# EuroCard_Backplane.net
KiCad netlist of a schematic drawn in EAGLE
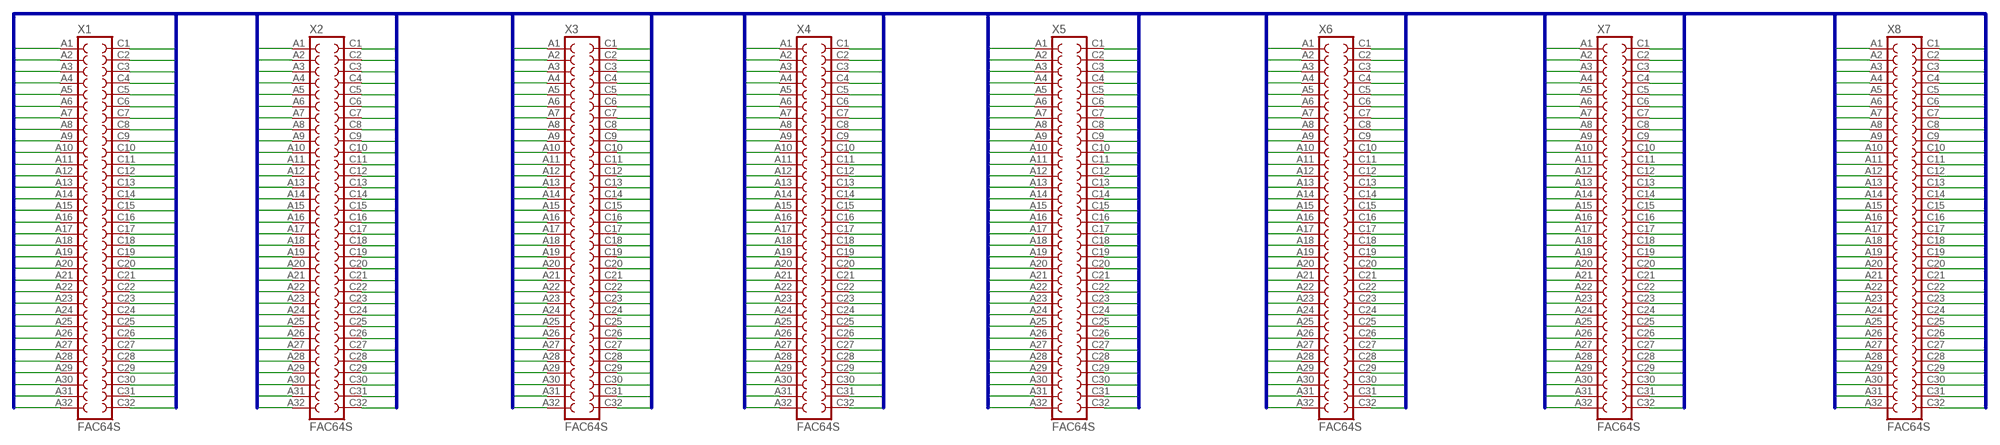
[diagram p0: schematic, sheet 1]

(export (version "E")
  (design (tool "Eeschema 10.0.6"))
  (components
    (comp (ref "X1")
      (value "FAC64S")
      (footprint "eagle-import:FAC64S")
      (libsource (lib "eagle-import") (part "FAC64S"))
    )
    (comp (ref "X2")
      (value "FAC64S")
      (footprint "eagle-import:FAC64S")
      (libsource (lib "eagle-import") (part "FAC64S"))
    )
    (comp (ref "X3")
      (value "FAC64S")
      (footprint "eagle-import:FAC64S")
      (libsource (lib "eagle-import") (part "FAC64S"))
    )
    (comp (ref "X4")
      (value "FAC64S")
      (footprint "eagle-import:FAC64S")
      (libsource (lib "eagle-import") (part "FAC64S"))
    )
    (comp (ref "X5")
      (value "FAC64S")
      (footprint "eagle-import:FAC64S")
      (libsource (lib "eagle-import") (part "FAC64S"))
    )
    (comp (ref "X6")
      (value "FAC64S")
      (footprint "eagle-import:FAC64S")
      (libsource (lib "eagle-import") (part "FAC64S"))
    )
    (comp (ref "X7")
      (value "FAC64S")
      (footprint "eagle-import:FAC64S")
      (libsource (lib "eagle-import") (part "FAC64S"))
    )
    (comp (ref "X8")
      (value "FAC64S")
      (footprint "eagle-import:FAC64S")
      (libsource (lib "eagle-import") (part "FAC64S"))
    )
  )
  (nets
    (net (code "1") (name "/A1") (class "Default")
      (node (ref "X1") (pin "A1") (pinfunction "A1_A1") (pintype "passive"))
      (node (ref "X2") (pin "A1") (pinfunction "A1_A1") (pintype "passive"))
      (node (ref "X3") (pin "A1") (pinfunction "A1_A1") (pintype "passive"))
      (node (ref "X4") (pin "A1") (pinfunction "A1_A1") (pintype "passive"))
      (node (ref "X5") (pin "A1") (pinfunction "A1_A1") (pintype "passive"))
      (node (ref "X6") (pin "A1") (pinfunction "A1_A1") (pintype "passive"))
      (node (ref "X7") (pin "A1") (pinfunction "A1_A1") (pintype "passive"))
      (node (ref "X8") (pin "A1") (pinfunction "A1_A1") (pintype "passive"))
    )
    (net (code "2") (name "/A2") (class "Default")
      (node (ref "X1") (pin "A2") (pinfunction "A2_A2") (pintype "passive"))
      (node (ref "X2") (pin "A2") (pinfunction "A2_A2") (pintype "passive"))
      (node (ref "X3") (pin "A2") (pinfunction "A2_A2") (pintype "passive"))
      (node (ref "X4") (pin "A2") (pinfunction "A2_A2") (pintype "passive"))
      (node (ref "X5") (pin "A2") (pinfunction "A2_A2") (pintype "passive"))
      (node (ref "X6") (pin "A2") (pinfunction "A2_A2") (pintype "passive"))
      (node (ref "X7") (pin "A2") (pinfunction "A2_A2") (pintype "passive"))
      (node (ref "X8") (pin "A2") (pinfunction "A2_A2") (pintype "passive"))
    )
    (net (code "3") (name "/A3") (class "Default")
      (node (ref "X1") (pin "A3") (pinfunction "A3_A3") (pintype "passive"))
      (node (ref "X2") (pin "A3") (pinfunction "A3_A3") (pintype "passive"))
      (node (ref "X3") (pin "A3") (pinfunction "A3_A3") (pintype "passive"))
      (node (ref "X4") (pin "A3") (pinfunction "A3_A3") (pintype "passive"))
      (node (ref "X5") (pin "A3") (pinfunction "A3_A3") (pintype "passive"))
      (node (ref "X6") (pin "A3") (pinfunction "A3_A3") (pintype "passive"))
      (node (ref "X7") (pin "A3") (pinfunction "A3_A3") (pintype "passive"))
      (node (ref "X8") (pin "A3") (pinfunction "A3_A3") (pintype "passive"))
    )
    (net (code "4") (name "/A4") (class "Default")
      (node (ref "X1") (pin "A4") (pinfunction "A4_A4") (pintype "passive"))
      (node (ref "X2") (pin "A4") (pinfunction "A4_A4") (pintype "passive"))
      (node (ref "X3") (pin "A4") (pinfunction "A4_A4") (pintype "passive"))
      (node (ref "X4") (pin "A4") (pinfunction "A4_A4") (pintype "passive"))
      (node (ref "X5") (pin "A4") (pinfunction "A4_A4") (pintype "passive"))
      (node (ref "X6") (pin "A4") (pinfunction "A4_A4") (pintype "passive"))
      (node (ref "X7") (pin "A4") (pinfunction "A4_A4") (pintype "passive"))
      (node (ref "X8") (pin "A4") (pinfunction "A4_A4") (pintype "passive"))
    )
    (net (code "5") (name "/A5") (class "Default")
      (node (ref "X1") (pin "A5") (pinfunction "A5_A5") (pintype "passive"))
      (node (ref "X2") (pin "A5") (pinfunction "A5_A5") (pintype "passive"))
      (node (ref "X3") (pin "A5") (pinfunction "A5_A5") (pintype "passive"))
      (node (ref "X4") (pin "A5") (pinfunction "A5_A5") (pintype "passive"))
      (node (ref "X5") (pin "A5") (pinfunction "A5_A5") (pintype "passive"))
      (node (ref "X6") (pin "A5") (pinfunction "A5_A5") (pintype "passive"))
      (node (ref "X7") (pin "A5") (pinfunction "A5_A5") (pintype "passive"))
      (node (ref "X8") (pin "A5") (pinfunction "A5_A5") (pintype "passive"))
    )
    (net (code "6") (name "/A6") (class "Default")
      (node (ref "X1") (pin "A6") (pinfunction "A6_A6") (pintype "passive"))
      (node (ref "X2") (pin "A6") (pinfunction "A6_A6") (pintype "passive"))
      (node (ref "X3") (pin "A6") (pinfunction "A6_A6") (pintype "passive"))
      (node (ref "X4") (pin "A6") (pinfunction "A6_A6") (pintype "passive"))
      (node (ref "X5") (pin "A6") (pinfunction "A6_A6") (pintype "passive"))
      (node (ref "X6") (pin "A6") (pinfunction "A6_A6") (pintype "passive"))
      (node (ref "X7") (pin "A6") (pinfunction "A6_A6") (pintype "passive"))
      (node (ref "X8") (pin "A6") (pinfunction "A6_A6") (pintype "passive"))
    )
    (net (code "7") (name "/A7") (class "Default")
      (node (ref "X1") (pin "A7") (pinfunction "A7_A7") (pintype "passive"))
      (node (ref "X2") (pin "A7") (pinfunction "A7_A7") (pintype "passive"))
      (node (ref "X3") (pin "A7") (pinfunction "A7_A7") (pintype "passive"))
      (node (ref "X4") (pin "A7") (pinfunction "A7_A7") (pintype "passive"))
      (node (ref "X5") (pin "A7") (pinfunction "A7_A7") (pintype "passive"))
      (node (ref "X6") (pin "A7") (pinfunction "A7_A7") (pintype "passive"))
      (node (ref "X7") (pin "A7") (pinfunction "A7_A7") (pintype "passive"))
      (node (ref "X8") (pin "A7") (pinfunction "A7_A7") (pintype "passive"))
    )
    (net (code "8") (name "/A8") (class "Default")
      (node (ref "X1") (pin "A8") (pinfunction "A8_A8") (pintype "passive"))
      (node (ref "X2") (pin "A8") (pinfunction "A8_A8") (pintype "passive"))
      (node (ref "X3") (pin "A8") (pinfunction "A8_A8") (pintype "passive"))
      (node (ref "X4") (pin "A8") (pinfunction "A8_A8") (pintype "passive"))
      (node (ref "X5") (pin "A8") (pinfunction "A8_A8") (pintype "passive"))
      (node (ref "X6") (pin "A8") (pinfunction "A8_A8") (pintype "passive"))
      (node (ref "X7") (pin "A8") (pinfunction "A8_A8") (pintype "passive"))
      (node (ref "X8") (pin "A8") (pinfunction "A8_A8") (pintype "passive"))
    )
    (net (code "9") (name "/A9") (class "Default")
      (node (ref "X1") (pin "A9") (pinfunction "A9_A9") (pintype "passive"))
      (node (ref "X2") (pin "A9") (pinfunction "A9_A9") (pintype "passive"))
      (node (ref "X3") (pin "A9") (pinfunction "A9_A9") (pintype "passive"))
      (node (ref "X4") (pin "A9") (pinfunction "A9_A9") (pintype "passive"))
      (node (ref "X5") (pin "A9") (pinfunction "A9_A9") (pintype "passive"))
      (node (ref "X6") (pin "A9") (pinfunction "A9_A9") (pintype "passive"))
      (node (ref "X7") (pin "A9") (pinfunction "A9_A9") (pintype "passive"))
      (node (ref "X8") (pin "A9") (pinfunction "A9_A9") (pintype "passive"))
    )
    (net (code "10") (name "/A10") (class "Default")
      (node (ref "X1") (pin "A10") (pinfunction "A10_A10") (pintype "passive"))
      (node (ref "X2") (pin "A10") (pinfunction "A10_A10") (pintype "passive"))
      (node (ref "X3") (pin "A10") (pinfunction "A10_A10") (pintype "passive"))
      (node (ref "X4") (pin "A10") (pinfunction "A10_A10") (pintype "passive"))
      (node (ref "X5") (pin "A10") (pinfunction "A10_A10") (pintype "passive"))
      (node (ref "X6") (pin "A10") (pinfunction "A10_A10") (pintype "passive"))
      (node (ref "X7") (pin "A10") (pinfunction "A10_A10") (pintype "passive"))
      (node (ref "X8") (pin "A10") (pinfunction "A10_A10") (pintype "passive"))
    )
    (net (code "11") (name "/A11") (class "Default")
      (node (ref "X1") (pin "A11") (pinfunction "A11_A11") (pintype "passive"))
      (node (ref "X2") (pin "A11") (pinfunction "A11_A11") (pintype "passive"))
      (node (ref "X3") (pin "A11") (pinfunction "A11_A11") (pintype "passive"))
      (node (ref "X4") (pin "A11") (pinfunction "A11_A11") (pintype "passive"))
      (node (ref "X5") (pin "A11") (pinfunction "A11_A11") (pintype "passive"))
      (node (ref "X6") (pin "A11") (pinfunction "A11_A11") (pintype "passive"))
      (node (ref "X7") (pin "A11") (pinfunction "A11_A11") (pintype "passive"))
      (node (ref "X8") (pin "A11") (pinfunction "A11_A11") (pintype "passive"))
    )
    (net (code "12") (name "/A12") (class "Default")
      (node (ref "X1") (pin "A12") (pinfunction "A12_A12") (pintype "passive"))
      (node (ref "X2") (pin "A12") (pinfunction "A12_A12") (pintype "passive"))
      (node (ref "X3") (pin "A12") (pinfunction "A12_A12") (pintype "passive"))
      (node (ref "X4") (pin "A12") (pinfunction "A12_A12") (pintype "passive"))
      (node (ref "X5") (pin "A12") (pinfunction "A12_A12") (pintype "passive"))
      (node (ref "X6") (pin "A12") (pinfunction "A12_A12") (pintype "passive"))
      (node (ref "X7") (pin "A12") (pinfunction "A12_A12") (pintype "passive"))
      (node (ref "X8") (pin "A12") (pinfunction "A12_A12") (pintype "passive"))
    )
    (net (code "13") (name "/A13") (class "Default")
      (node (ref "X1") (pin "A13") (pinfunction "A13_A13") (pintype "passive"))
      (node (ref "X2") (pin "A13") (pinfunction "A13_A13") (pintype "passive"))
      (node (ref "X3") (pin "A13") (pinfunction "A13_A13") (pintype "passive"))
      (node (ref "X4") (pin "A13") (pinfunction "A13_A13") (pintype "passive"))
      (node (ref "X5") (pin "A13") (pinfunction "A13_A13") (pintype "passive"))
      (node (ref "X6") (pin "A13") (pinfunction "A13_A13") (pintype "passive"))
      (node (ref "X7") (pin "A13") (pinfunction "A13_A13") (pintype "passive"))
      (node (ref "X8") (pin "A13") (pinfunction "A13_A13") (pintype "passive"))
    )
    (net (code "14") (name "/A14") (class "Default")
      (node (ref "X1") (pin "A14") (pinfunction "A14_A14") (pintype "passive"))
      (node (ref "X2") (pin "A14") (pinfunction "A14_A14") (pintype "passive"))
      (node (ref "X3") (pin "A14") (pinfunction "A14_A14") (pintype "passive"))
      (node (ref "X4") (pin "A14") (pinfunction "A14_A14") (pintype "passive"))
      (node (ref "X5") (pin "A14") (pinfunction "A14_A14") (pintype "passive"))
      (node (ref "X6") (pin "A14") (pinfunction "A14_A14") (pintype "passive"))
      (node (ref "X7") (pin "A14") (pinfunction "A14_A14") (pintype "passive"))
      (node (ref "X8") (pin "A14") (pinfunction "A14_A14") (pintype "passive"))
    )
    (net (code "15") (name "/A15") (class "Default")
      (node (ref "X1") (pin "A15") (pinfunction "A15_A15") (pintype "passive"))
      (node (ref "X2") (pin "A15") (pinfunction "A15_A15") (pintype "passive"))
      (node (ref "X3") (pin "A15") (pinfunction "A15_A15") (pintype "passive"))
      (node (ref "X4") (pin "A15") (pinfunction "A15_A15") (pintype "passive"))
      (node (ref "X5") (pin "A15") (pinfunction "A15_A15") (pintype "passive"))
      (node (ref "X6") (pin "A15") (pinfunction "A15_A15") (pintype "passive"))
      (node (ref "X7") (pin "A15") (pinfunction "A15_A15") (pintype "passive"))
      (node (ref "X8") (pin "A15") (pinfunction "A15_A15") (pintype "passive"))
    )
    (net (code "16") (name "/A16") (class "Default")
      (node (ref "X1") (pin "A16") (pinfunction "A16_A16") (pintype "passive"))
      (node (ref "X2") (pin "A16") (pinfunction "A16_A16") (pintype "passive"))
      (node (ref "X3") (pin "A16") (pinfunction "A16_A16") (pintype "passive"))
      (node (ref "X4") (pin "A16") (pinfunction "A16_A16") (pintype "passive"))
      (node (ref "X5") (pin "A16") (pinfunction "A16_A16") (pintype "passive"))
      (node (ref "X6") (pin "A16") (pinfunction "A16_A16") (pintype "passive"))
      (node (ref "X7") (pin "A16") (pinfunction "A16_A16") (pintype "passive"))
      (node (ref "X8") (pin "A16") (pinfunction "A16_A16") (pintype "passive"))
    )
    (net (code "17") (name "/A17") (class "Default")
      (node (ref "X1") (pin "A17") (pinfunction "A17_A17") (pintype "passive"))
      (node (ref "X2") (pin "A17") (pinfunction "A17_A17") (pintype "passive"))
      (node (ref "X3") (pin "A17") (pinfunction "A17_A17") (pintype "passive"))
      (node (ref "X4") (pin "A17") (pinfunction "A17_A17") (pintype "passive"))
      (node (ref "X5") (pin "A17") (pinfunction "A17_A17") (pintype "passive"))
      (node (ref "X6") (pin "A17") (pinfunction "A17_A17") (pintype "passive"))
      (node (ref "X7") (pin "A17") (pinfunction "A17_A17") (pintype "passive"))
      (node (ref "X8") (pin "A17") (pinfunction "A17_A17") (pintype "passive"))
    )
    (net (code "18") (name "/A18") (class "Default")
      (node (ref "X1") (pin "A18") (pinfunction "A18_A18") (pintype "passive"))
      (node (ref "X2") (pin "A18") (pinfunction "A18_A18") (pintype "passive"))
      (node (ref "X3") (pin "A18") (pinfunction "A18_A18") (pintype "passive"))
      (node (ref "X4") (pin "A18") (pinfunction "A18_A18") (pintype "passive"))
      (node (ref "X5") (pin "A18") (pinfunction "A18_A18") (pintype "passive"))
      (node (ref "X6") (pin "A18") (pinfunction "A18_A18") (pintype "passive"))
      (node (ref "X7") (pin "A18") (pinfunction "A18_A18") (pintype "passive"))
      (node (ref "X8") (pin "A18") (pinfunction "A18_A18") (pintype "passive"))
    )
    (net (code "19") (name "/A19") (class "Default")
      (node (ref "X1") (pin "A19") (pinfunction "A19_A19") (pintype "passive"))
      (node (ref "X2") (pin "A19") (pinfunction "A19_A19") (pintype "passive"))
      (node (ref "X3") (pin "A19") (pinfunction "A19_A19") (pintype "passive"))
      (node (ref "X4") (pin "A19") (pinfunction "A19_A19") (pintype "passive"))
      (node (ref "X5") (pin "A19") (pinfunction "A19_A19") (pintype "passive"))
      (node (ref "X6") (pin "A19") (pinfunction "A19_A19") (pintype "passive"))
      (node (ref "X7") (pin "A19") (pinfunction "A19_A19") (pintype "passive"))
      (node (ref "X8") (pin "A19") (pinfunction "A19_A19") (pintype "passive"))
    )
    (net (code "20") (name "/A20") (class "Default")
      (node (ref "X1") (pin "A20") (pinfunction "A20_A20") (pintype "passive"))
      (node (ref "X2") (pin "A20") (pinfunction "A20_A20") (pintype "passive"))
      (node (ref "X3") (pin "A20") (pinfunction "A20_A20") (pintype "passive"))
      (node (ref "X4") (pin "A20") (pinfunction "A20_A20") (pintype "passive"))
      (node (ref "X5") (pin "A20") (pinfunction "A20_A20") (pintype "passive"))
      (node (ref "X6") (pin "A20") (pinfunction "A20_A20") (pintype "passive"))
      (node (ref "X7") (pin "A20") (pinfunction "A20_A20") (pintype "passive"))
      (node (ref "X8") (pin "A20") (pinfunction "A20_A20") (pintype "passive"))
    )
    (net (code "21") (name "/A21") (class "Default")
      (node (ref "X1") (pin "A21") (pinfunction "A21_A21") (pintype "passive"))
      (node (ref "X2") (pin "A21") (pinfunction "A21_A21") (pintype "passive"))
      (node (ref "X3") (pin "A21") (pinfunction "A21_A21") (pintype "passive"))
      (node (ref "X4") (pin "A21") (pinfunction "A21_A21") (pintype "passive"))
      (node (ref "X5") (pin "A21") (pinfunction "A21_A21") (pintype "passive"))
      (node (ref "X6") (pin "A21") (pinfunction "A21_A21") (pintype "passive"))
      (node (ref "X7") (pin "A21") (pinfunction "A21_A21") (pintype "passive"))
      (node (ref "X8") (pin "A21") (pinfunction "A21_A21") (pintype "passive"))
    )
    (net (code "22") (name "/A22") (class "Default")
      (node (ref "X1") (pin "A22") (pinfunction "A22_A22") (pintype "passive"))
      (node (ref "X2") (pin "A22") (pinfunction "A22_A22") (pintype "passive"))
      (node (ref "X3") (pin "A22") (pinfunction "A22_A22") (pintype "passive"))
      (node (ref "X4") (pin "A22") (pinfunction "A22_A22") (pintype "passive"))
      (node (ref "X5") (pin "A22") (pinfunction "A22_A22") (pintype "passive"))
      (node (ref "X6") (pin "A22") (pinfunction "A22_A22") (pintype "passive"))
      (node (ref "X7") (pin "A22") (pinfunction "A22_A22") (pintype "passive"))
      (node (ref "X8") (pin "A22") (pinfunction "A22_A22") (pintype "passive"))
    )
    (net (code "23") (name "/A23") (class "Default")
      (node (ref "X1") (pin "A23") (pinfunction "A23_A23") (pintype "passive"))
      (node (ref "X2") (pin "A23") (pinfunction "A23_A23") (pintype "passive"))
      (node (ref "X3") (pin "A23") (pinfunction "A23_A23") (pintype "passive"))
      (node (ref "X4") (pin "A23") (pinfunction "A23_A23") (pintype "passive"))
      (node (ref "X5") (pin "A23") (pinfunction "A23_A23") (pintype "passive"))
      (node (ref "X6") (pin "A23") (pinfunction "A23_A23") (pintype "passive"))
      (node (ref "X7") (pin "A23") (pinfunction "A23_A23") (pintype "passive"))
      (node (ref "X8") (pin "A23") (pinfunction "A23_A23") (pintype "passive"))
    )
    (net (code "24") (name "/A24") (class "Default")
      (node (ref "X1") (pin "A24") (pinfunction "A24_A24") (pintype "passive"))
      (node (ref "X2") (pin "A24") (pinfunction "A24_A24") (pintype "passive"))
      (node (ref "X3") (pin "A24") (pinfunction "A24_A24") (pintype "passive"))
      (node (ref "X4") (pin "A24") (pinfunction "A24_A24") (pintype "passive"))
      (node (ref "X5") (pin "A24") (pinfunction "A24_A24") (pintype "passive"))
      (node (ref "X6") (pin "A24") (pinfunction "A24_A24") (pintype "passive"))
      (node (ref "X7") (pin "A24") (pinfunction "A24_A24") (pintype "passive"))
      (node (ref "X8") (pin "A24") (pinfunction "A24_A24") (pintype "passive"))
    )
    (net (code "25") (name "/A25") (class "Default")
      (node (ref "X1") (pin "A25") (pinfunction "A25_A25") (pintype "passive"))
      (node (ref "X2") (pin "A25") (pinfunction "A25_A25") (pintype "passive"))
      (node (ref "X3") (pin "A25") (pinfunction "A25_A25") (pintype "passive"))
      (node (ref "X4") (pin "A25") (pinfunction "A25_A25") (pintype "passive"))
      (node (ref "X5") (pin "A25") (pinfunction "A25_A25") (pintype "passive"))
      (node (ref "X6") (pin "A25") (pinfunction "A25_A25") (pintype "passive"))
      (node (ref "X7") (pin "A25") (pinfunction "A25_A25") (pintype "passive"))
      (node (ref "X8") (pin "A25") (pinfunction "A25_A25") (pintype "passive"))
    )
    (net (code "26") (name "/A26") (class "Default")
      (node (ref "X1") (pin "A26") (pinfunction "A26_A26") (pintype "passive"))
      (node (ref "X2") (pin "A26") (pinfunction "A26_A26") (pintype "passive"))
      (node (ref "X3") (pin "A26") (pinfunction "A26_A26") (pintype "passive"))
      (node (ref "X4") (pin "A26") (pinfunction "A26_A26") (pintype "passive"))
      (node (ref "X5") (pin "A26") (pinfunction "A26_A26") (pintype "passive"))
      (node (ref "X6") (pin "A26") (pinfunction "A26_A26") (pintype "passive"))
      (node (ref "X7") (pin "A26") (pinfunction "A26_A26") (pintype "passive"))
      (node (ref "X8") (pin "A26") (pinfunction "A26_A26") (pintype "passive"))
    )
    (net (code "27") (name "/A27") (class "Default")
      (node (ref "X1") (pin "A27") (pinfunction "A27_A27") (pintype "passive"))
      (node (ref "X2") (pin "A27") (pinfunction "A27_A27") (pintype "passive"))
      (node (ref "X3") (pin "A27") (pinfunction "A27_A27") (pintype "passive"))
      (node (ref "X4") (pin "A27") (pinfunction "A27_A27") (pintype "passive"))
      (node (ref "X5") (pin "A27") (pinfunction "A27_A27") (pintype "passive"))
      (node (ref "X6") (pin "A27") (pinfunction "A27_A27") (pintype "passive"))
      (node (ref "X7") (pin "A27") (pinfunction "A27_A27") (pintype "passive"))
      (node (ref "X8") (pin "A27") (pinfunction "A27_A27") (pintype "passive"))
    )
    (net (code "28") (name "/A28") (class "Default")
      (node (ref "X1") (pin "A28") (pinfunction "A28_A28") (pintype "passive"))
      (node (ref "X2") (pin "A28") (pinfunction "A28_A28") (pintype "passive"))
      (node (ref "X3") (pin "A28") (pinfunction "A28_A28") (pintype "passive"))
      (node (ref "X4") (pin "A28") (pinfunction "A28_A28") (pintype "passive"))
      (node (ref "X5") (pin "A28") (pinfunction "A28_A28") (pintype "passive"))
      (node (ref "X6") (pin "A28") (pinfunction "A28_A28") (pintype "passive"))
      (node (ref "X7") (pin "A28") (pinfunction "A28_A28") (pintype "passive"))
      (node (ref "X8") (pin "A28") (pinfunction "A28_A28") (pintype "passive"))
    )
    (net (code "29") (name "/A29") (class "Default")
      (node (ref "X1") (pin "A29") (pinfunction "A29_A29") (pintype "passive"))
      (node (ref "X2") (pin "A29") (pinfunction "A29_A29") (pintype "passive"))
      (node (ref "X3") (pin "A29") (pinfunction "A29_A29") (pintype "passive"))
      (node (ref "X4") (pin "A29") (pinfunction "A29_A29") (pintype "passive"))
      (node (ref "X5") (pin "A29") (pinfunction "A29_A29") (pintype "passive"))
      (node (ref "X6") (pin "A29") (pinfunction "A29_A29") (pintype "passive"))
      (node (ref "X7") (pin "A29") (pinfunction "A29_A29") (pintype "passive"))
      (node (ref "X8") (pin "A29") (pinfunction "A29_A29") (pintype "passive"))
    )
    (net (code "30") (name "/A30") (class "Default")
      (node (ref "X1") (pin "A30") (pinfunction "A30_A30") (pintype "passive"))
      (node (ref "X2") (pin "A30") (pinfunction "A30_A30") (pintype "passive"))
      (node (ref "X3") (pin "A30") (pinfunction "A30_A30") (pintype "passive"))
      (node (ref "X4") (pin "A30") (pinfunction "A30_A30") (pintype "passive"))
      (node (ref "X5") (pin "A30") (pinfunction "A30_A30") (pintype "passive"))
      (node (ref "X6") (pin "A30") (pinfunction "A30_A30") (pintype "passive"))
      (node (ref "X7") (pin "A30") (pinfunction "A30_A30") (pintype "passive"))
      (node (ref "X8") (pin "A30") (pinfunction "A30_A30") (pintype "passive"))
    )
    (net (code "31") (name "/A31") (class "Default")
      (node (ref "X1") (pin "A31") (pinfunction "A31_A31") (pintype "passive"))
      (node (ref "X2") (pin "A31") (pinfunction "A31_A31") (pintype "passive"))
      (node (ref "X3") (pin "A31") (pinfunction "A31_A31") (pintype "passive"))
      (node (ref "X4") (pin "A31") (pinfunction "A31_A31") (pintype "passive"))
      (node (ref "X5") (pin "A31") (pinfunction "A31_A31") (pintype "passive"))
      (node (ref "X6") (pin "A31") (pinfunction "A31_A31") (pintype "passive"))
      (node (ref "X7") (pin "A31") (pinfunction "A31_A31") (pintype "passive"))
      (node (ref "X8") (pin "A31") (pinfunction "A31_A31") (pintype "passive"))
    )
    (net (code "32") (name "/A32") (class "Default")
      (node (ref "X1") (pin "A32") (pinfunction "A32_A32") (pintype "passive"))
      (node (ref "X2") (pin "A32") (pinfunction "A32_A32") (pintype "passive"))
      (node (ref "X3") (pin "A32") (pinfunction "A32_A32") (pintype "passive"))
      (node (ref "X4") (pin "A32") (pinfunction "A32_A32") (pintype "passive"))
      (node (ref "X5") (pin "A32") (pinfunction "A32_A32") (pintype "passive"))
      (node (ref "X6") (pin "A32") (pinfunction "A32_A32") (pintype "passive"))
      (node (ref "X7") (pin "A32") (pinfunction "A32_A32") (pintype "passive"))
      (node (ref "X8") (pin "A32") (pinfunction "A32_A32") (pintype "passive"))
    )
    (net (code "33") (name "/C1") (class "Default")
      (node (ref "X1") (pin "C1") (pinfunction "C1_C1") (pintype "passive"))
      (node (ref "X2") (pin "C1") (pinfunction "C1_C1") (pintype "passive"))
      (node (ref "X3") (pin "C1") (pinfunction "C1_C1") (pintype "passive"))
      (node (ref "X4") (pin "C1") (pinfunction "C1_C1") (pintype "passive"))
      (node (ref "X5") (pin "C1") (pinfunction "C1_C1") (pintype "passive"))
      (node (ref "X6") (pin "C1") (pinfunction "C1_C1") (pintype "passive"))
      (node (ref "X7") (pin "C1") (pinfunction "C1_C1") (pintype "passive"))
      (node (ref "X8") (pin "C1") (pinfunction "C1_C1") (pintype "passive"))
    )
    (net (code "34") (name "/C2") (class "Default")
      (node (ref "X1") (pin "C2") (pinfunction "C2_C2") (pintype "passive"))
      (node (ref "X2") (pin "C2") (pinfunction "C2_C2") (pintype "passive"))
      (node (ref "X3") (pin "C2") (pinfunction "C2_C2") (pintype "passive"))
      (node (ref "X4") (pin "C2") (pinfunction "C2_C2") (pintype "passive"))
      (node (ref "X5") (pin "C2") (pinfunction "C2_C2") (pintype "passive"))
      (node (ref "X6") (pin "C2") (pinfunction "C2_C2") (pintype "passive"))
      (node (ref "X7") (pin "C2") (pinfunction "C2_C2") (pintype "passive"))
      (node (ref "X8") (pin "C2") (pinfunction "C2_C2") (pintype "passive"))
    )
    (net (code "35") (name "/C3") (class "Default")
      (node (ref "X1") (pin "C3") (pinfunction "C3_C3") (pintype "passive"))
      (node (ref "X2") (pin "C3") (pinfunction "C3_C3") (pintype "passive"))
      (node (ref "X3") (pin "C3") (pinfunction "C3_C3") (pintype "passive"))
      (node (ref "X4") (pin "C3") (pinfunction "C3_C3") (pintype "passive"))
      (node (ref "X5") (pin "C3") (pinfunction "C3_C3") (pintype "passive"))
      (node (ref "X6") (pin "C3") (pinfunction "C3_C3") (pintype "passive"))
      (node (ref "X7") (pin "C3") (pinfunction "C3_C3") (pintype "passive"))
      (node (ref "X8") (pin "C3") (pinfunction "C3_C3") (pintype "passive"))
    )
    (net (code "36") (name "/C4") (class "Default")
      (node (ref "X1") (pin "C4") (pinfunction "C4_C4") (pintype "passive"))
      (node (ref "X2") (pin "C4") (pinfunction "C4_C4") (pintype "passive"))
      (node (ref "X3") (pin "C4") (pinfunction "C4_C4") (pintype "passive"))
      (node (ref "X4") (pin "C4") (pinfunction "C4_C4") (pintype "passive"))
      (node (ref "X5") (pin "C4") (pinfunction "C4_C4") (pintype "passive"))
      (node (ref "X6") (pin "C4") (pinfunction "C4_C4") (pintype "passive"))
      (node (ref "X7") (pin "C4") (pinfunction "C4_C4") (pintype "passive"))
      (node (ref "X8") (pin "C4") (pinfunction "C4_C4") (pintype "passive"))
    )
    (net (code "37") (name "/C5") (class "Default")
      (node (ref "X1") (pin "C5") (pinfunction "C5_C5") (pintype "passive"))
      (node (ref "X2") (pin "C5") (pinfunction "C5_C5") (pintype "passive"))
      (node (ref "X3") (pin "C5") (pinfunction "C5_C5") (pintype "passive"))
      (node (ref "X4") (pin "C5") (pinfunction "C5_C5") (pintype "passive"))
      (node (ref "X5") (pin "C5") (pinfunction "C5_C5") (pintype "passive"))
      (node (ref "X6") (pin "C5") (pinfunction "C5_C5") (pintype "passive"))
      (node (ref "X7") (pin "C5") (pinfunction "C5_C5") (pintype "passive"))
      (node (ref "X8") (pin "C5") (pinfunction "C5_C5") (pintype "passive"))
    )
    (net (code "38") (name "/C6") (class "Default")
      (node (ref "X1") (pin "C6") (pinfunction "C6_C6") (pintype "passive"))
      (node (ref "X2") (pin "C6") (pinfunction "C6_C6") (pintype "passive"))
      (node (ref "X3") (pin "C6") (pinfunction "C6_C6") (pintype "passive"))
      (node (ref "X4") (pin "C6") (pinfunction "C6_C6") (pintype "passive"))
      (node (ref "X5") (pin "C6") (pinfunction "C6_C6") (pintype "passive"))
      (node (ref "X6") (pin "C6") (pinfunction "C6_C6") (pintype "passive"))
      (node (ref "X7") (pin "C6") (pinfunction "C6_C6") (pintype "passive"))
      (node (ref "X8") (pin "C6") (pinfunction "C6_C6") (pintype "passive"))
    )
    (net (code "39") (name "/C7") (class "Default")
      (node (ref "X1") (pin "C7") (pinfunction "C7_C7") (pintype "passive"))
      (node (ref "X2") (pin "C7") (pinfunction "C7_C7") (pintype "passive"))
      (node (ref "X3") (pin "C7") (pinfunction "C7_C7") (pintype "passive"))
      (node (ref "X4") (pin "C7") (pinfunction "C7_C7") (pintype "passive"))
      (node (ref "X5") (pin "C7") (pinfunction "C7_C7") (pintype "passive"))
      (node (ref "X6") (pin "C7") (pinfunction "C7_C7") (pintype "passive"))
      (node (ref "X7") (pin "C7") (pinfunction "C7_C7") (pintype "passive"))
      (node (ref "X8") (pin "C7") (pinfunction "C7_C7") (pintype "passive"))
    )
    (net (code "40") (name "/C8") (class "Default")
      (node (ref "X1") (pin "C8") (pinfunction "C8_C8") (pintype "passive"))
      (node (ref "X2") (pin "C8") (pinfunction "C8_C8") (pintype "passive"))
      (node (ref "X3") (pin "C8") (pinfunction "C8_C8") (pintype "passive"))
      (node (ref "X4") (pin "C8") (pinfunction "C8_C8") (pintype "passive"))
      (node (ref "X5") (pin "C8") (pinfunction "C8_C8") (pintype "passive"))
      (node (ref "X6") (pin "C8") (pinfunction "C8_C8") (pintype "passive"))
      (node (ref "X7") (pin "C8") (pinfunction "C8_C8") (pintype "passive"))
      (node (ref "X8") (pin "C8") (pinfunction "C8_C8") (pintype "passive"))
    )
    (net (code "41") (name "/C9") (class "Default")
      (node (ref "X1") (pin "C9") (pinfunction "C9_C9") (pintype "passive"))
      (node (ref "X2") (pin "C9") (pinfunction "C9_C9") (pintype "passive"))
      (node (ref "X3") (pin "C9") (pinfunction "C9_C9") (pintype "passive"))
      (node (ref "X4") (pin "C9") (pinfunction "C9_C9") (pintype "passive"))
      (node (ref "X5") (pin "C9") (pinfunction "C9_C9") (pintype "passive"))
      (node (ref "X6") (pin "C9") (pinfunction "C9_C9") (pintype "passive"))
      (node (ref "X7") (pin "C9") (pinfunction "C9_C9") (pintype "passive"))
      (node (ref "X8") (pin "C9") (pinfunction "C9_C9") (pintype "passive"))
    )
    (net (code "42") (name "/C10") (class "Default")
      (node (ref "X1") (pin "C10") (pinfunction "C10_C10") (pintype "passive"))
      (node (ref "X2") (pin "C10") (pinfunction "C10_C10") (pintype "passive"))
      (node (ref "X3") (pin "C10") (pinfunction "C10_C10") (pintype "passive"))
      (node (ref "X4") (pin "C10") (pinfunction "C10_C10") (pintype "passive"))
      (node (ref "X5") (pin "C10") (pinfunction "C10_C10") (pintype "passive"))
      (node (ref "X6") (pin "C10") (pinfunction "C10_C10") (pintype "passive"))
      (node (ref "X7") (pin "C10") (pinfunction "C10_C10") (pintype "passive"))
      (node (ref "X8") (pin "C10") (pinfunction "C10_C10") (pintype "passive"))
    )
    (net (code "43") (name "/C11") (class "Default")
      (node (ref "X1") (pin "C11") (pinfunction "C11_C11") (pintype "passive"))
      (node (ref "X2") (pin "C11") (pinfunction "C11_C11") (pintype "passive"))
      (node (ref "X3") (pin "C11") (pinfunction "C11_C11") (pintype "passive"))
      (node (ref "X4") (pin "C11") (pinfunction "C11_C11") (pintype "passive"))
      (node (ref "X5") (pin "C11") (pinfunction "C11_C11") (pintype "passive"))
      (node (ref "X6") (pin "C11") (pinfunction "C11_C11") (pintype "passive"))
      (node (ref "X7") (pin "C11") (pinfunction "C11_C11") (pintype "passive"))
      (node (ref "X8") (pin "C11") (pinfunction "C11_C11") (pintype "passive"))
    )
    (net (code "44") (name "/C12") (class "Default")
      (node (ref "X1") (pin "C12") (pinfunction "C12_C12") (pintype "passive"))
      (node (ref "X2") (pin "C12") (pinfunction "C12_C12") (pintype "passive"))
      (node (ref "X3") (pin "C12") (pinfunction "C12_C12") (pintype "passive"))
      (node (ref "X4") (pin "C12") (pinfunction "C12_C12") (pintype "passive"))
      (node (ref "X5") (pin "C12") (pinfunction "C12_C12") (pintype "passive"))
      (node (ref "X6") (pin "C12") (pinfunction "C12_C12") (pintype "passive"))
      (node (ref "X7") (pin "C12") (pinfunction "C12_C12") (pintype "passive"))
      (node (ref "X8") (pin "C12") (pinfunction "C12_C12") (pintype "passive"))
    )
    (net (code "45") (name "/C13") (class "Default")
      (node (ref "X1") (pin "C13") (pinfunction "C13_C13") (pintype "passive"))
      (node (ref "X2") (pin "C13") (pinfunction "C13_C13") (pintype "passive"))
      (node (ref "X3") (pin "C13") (pinfunction "C13_C13") (pintype "passive"))
      (node (ref "X4") (pin "C13") (pinfunction "C13_C13") (pintype "passive"))
      (node (ref "X5") (pin "C13") (pinfunction "C13_C13") (pintype "passive"))
      (node (ref "X6") (pin "C13") (pinfunction "C13_C13") (pintype "passive"))
      (node (ref "X7") (pin "C13") (pinfunction "C13_C13") (pintype "passive"))
      (node (ref "X8") (pin "C13") (pinfunction "C13_C13") (pintype "passive"))
    )
    (net (code "46") (name "/C14") (class "Default")
      (node (ref "X1") (pin "C14") (pinfunction "C14_C14") (pintype "passive"))
      (node (ref "X2") (pin "C14") (pinfunction "C14_C14") (pintype "passive"))
      (node (ref "X3") (pin "C14") (pinfunction "C14_C14") (pintype "passive"))
      (node (ref "X4") (pin "C14") (pinfunction "C14_C14") (pintype "passive"))
      (node (ref "X5") (pin "C14") (pinfunction "C14_C14") (pintype "passive"))
      (node (ref "X6") (pin "C14") (pinfunction "C14_C14") (pintype "passive"))
      (node (ref "X7") (pin "C14") (pinfunction "C14_C14") (pintype "passive"))
      (node (ref "X8") (pin "C14") (pinfunction "C14_C14") (pintype "passive"))
    )
    (net (code "47") (name "/C15") (class "Default")
      (node (ref "X1") (pin "C15") (pinfunction "C15_C15") (pintype "passive"))
      (node (ref "X2") (pin "C15") (pinfunction "C15_C15") (pintype "passive"))
      (node (ref "X3") (pin "C15") (pinfunction "C15_C15") (pintype "passive"))
      (node (ref "X4") (pin "C15") (pinfunction "C15_C15") (pintype "passive"))
      (node (ref "X5") (pin "C15") (pinfunction "C15_C15") (pintype "passive"))
      (node (ref "X6") (pin "C15") (pinfunction "C15_C15") (pintype "passive"))
      (node (ref "X7") (pin "C15") (pinfunction "C15_C15") (pintype "passive"))
      (node (ref "X8") (pin "C15") (pinfunction "C15_C15") (pintype "passive"))
    )
    (net (code "48") (name "/C16") (class "Default")
      (node (ref "X1") (pin "C16") (pinfunction "C16_C16") (pintype "passive"))
      (node (ref "X2") (pin "C16") (pinfunction "C16_C16") (pintype "passive"))
      (node (ref "X3") (pin "C16") (pinfunction "C16_C16") (pintype "passive"))
      (node (ref "X4") (pin "C16") (pinfunction "C16_C16") (pintype "passive"))
      (node (ref "X5") (pin "C16") (pinfunction "C16_C16") (pintype "passive"))
      (node (ref "X6") (pin "C16") (pinfunction "C16_C16") (pintype "passive"))
      (node (ref "X7") (pin "C16") (pinfunction "C16_C16") (pintype "passive"))
      (node (ref "X8") (pin "C16") (pinfunction "C16_C16") (pintype "passive"))
    )
    (net (code "49") (name "/C17") (class "Default")
      (node (ref "X1") (pin "C17") (pinfunction "C17_C17") (pintype "passive"))
      (node (ref "X2") (pin "C17") (pinfunction "C17_C17") (pintype "passive"))
      (node (ref "X3") (pin "C17") (pinfunction "C17_C17") (pintype "passive"))
      (node (ref "X4") (pin "C17") (pinfunction "C17_C17") (pintype "passive"))
      (node (ref "X5") (pin "C17") (pinfunction "C17_C17") (pintype "passive"))
      (node (ref "X6") (pin "C17") (pinfunction "C17_C17") (pintype "passive"))
      (node (ref "X7") (pin "C17") (pinfunction "C17_C17") (pintype "passive"))
      (node (ref "X8") (pin "C17") (pinfunction "C17_C17") (pintype "passive"))
    )
    (net (code "50") (name "/C18") (class "Default")
      (node (ref "X1") (pin "C18") (pinfunction "C18_C18") (pintype "passive"))
      (node (ref "X2") (pin "C18") (pinfunction "C18_C18") (pintype "passive"))
      (node (ref "X3") (pin "C18") (pinfunction "C18_C18") (pintype "passive"))
      (node (ref "X4") (pin "C18") (pinfunction "C18_C18") (pintype "passive"))
      (node (ref "X5") (pin "C18") (pinfunction "C18_C18") (pintype "passive"))
      (node (ref "X6") (pin "C18") (pinfunction "C18_C18") (pintype "passive"))
      (node (ref "X7") (pin "C18") (pinfunction "C18_C18") (pintype "passive"))
      (node (ref "X8") (pin "C18") (pinfunction "C18_C18") (pintype "passive"))
    )
    (net (code "51") (name "/C19") (class "Default")
      (node (ref "X1") (pin "C19") (pinfunction "C19_C19") (pintype "passive"))
      (node (ref "X2") (pin "C19") (pinfunction "C19_C19") (pintype "passive"))
      (node (ref "X3") (pin "C19") (pinfunction "C19_C19") (pintype "passive"))
      (node (ref "X4") (pin "C19") (pinfunction "C19_C19") (pintype "passive"))
      (node (ref "X5") (pin "C19") (pinfunction "C19_C19") (pintype "passive"))
      (node (ref "X6") (pin "C19") (pinfunction "C19_C19") (pintype "passive"))
      (node (ref "X7") (pin "C19") (pinfunction "C19_C19") (pintype "passive"))
      (node (ref "X8") (pin "C19") (pinfunction "C19_C19") (pintype "passive"))
    )
    (net (code "52") (name "/C20") (class "Default")
      (node (ref "X1") (pin "C20") (pinfunction "C20_C20") (pintype "passive"))
      (node (ref "X2") (pin "C20") (pinfunction "C20_C20") (pintype "passive"))
      (node (ref "X3") (pin "C20") (pinfunction "C20_C20") (pintype "passive"))
      (node (ref "X4") (pin "C20") (pinfunction "C20_C20") (pintype "passive"))
      (node (ref "X5") (pin "C20") (pinfunction "C20_C20") (pintype "passive"))
      (node (ref "X6") (pin "C20") (pinfunction "C20_C20") (pintype "passive"))
      (node (ref "X7") (pin "C20") (pinfunction "C20_C20") (pintype "passive"))
      (node (ref "X8") (pin "C20") (pinfunction "C20_C20") (pintype "passive"))
    )
    (net (code "53") (name "/C21") (class "Default")
      (node (ref "X1") (pin "C21") (pinfunction "C21_C21") (pintype "passive"))
      (node (ref "X2") (pin "C21") (pinfunction "C21_C21") (pintype "passive"))
      (node (ref "X3") (pin "C21") (pinfunction "C21_C21") (pintype "passive"))
      (node (ref "X4") (pin "C21") (pinfunction "C21_C21") (pintype "passive"))
      (node (ref "X5") (pin "C21") (pinfunction "C21_C21") (pintype "passive"))
      (node (ref "X6") (pin "C21") (pinfunction "C21_C21") (pintype "passive"))
      (node (ref "X7") (pin "C21") (pinfunction "C21_C21") (pintype "passive"))
      (node (ref "X8") (pin "C21") (pinfunction "C21_C21") (pintype "passive"))
    )
    (net (code "54") (name "/C22") (class "Default")
      (node (ref "X1") (pin "C22") (pinfunction "C22_C22") (pintype "passive"))
      (node (ref "X2") (pin "C22") (pinfunction "C22_C22") (pintype "passive"))
      (node (ref "X3") (pin "C22") (pinfunction "C22_C22") (pintype "passive"))
      (node (ref "X4") (pin "C22") (pinfunction "C22_C22") (pintype "passive"))
      (node (ref "X5") (pin "C22") (pinfunction "C22_C22") (pintype "passive"))
      (node (ref "X6") (pin "C22") (pinfunction "C22_C22") (pintype "passive"))
      (node (ref "X7") (pin "C22") (pinfunction "C22_C22") (pintype "passive"))
      (node (ref "X8") (pin "C22") (pinfunction "C22_C22") (pintype "passive"))
    )
    (net (code "55") (name "/C23") (class "Default")
      (node (ref "X1") (pin "C23") (pinfunction "C23_C23") (pintype "passive"))
      (node (ref "X2") (pin "C23") (pinfunction "C23_C23") (pintype "passive"))
      (node (ref "X3") (pin "C23") (pinfunction "C23_C23") (pintype "passive"))
      (node (ref "X4") (pin "C23") (pinfunction "C23_C23") (pintype "passive"))
      (node (ref "X5") (pin "C23") (pinfunction "C23_C23") (pintype "passive"))
      (node (ref "X6") (pin "C23") (pinfunction "C23_C23") (pintype "passive"))
      (node (ref "X7") (pin "C23") (pinfunction "C23_C23") (pintype "passive"))
      (node (ref "X8") (pin "C23") (pinfunction "C23_C23") (pintype "passive"))
    )
    (net (code "56") (name "/C24") (class "Default")
      (node (ref "X1") (pin "C24") (pinfunction "C24_C24") (pintype "passive"))
      (node (ref "X2") (pin "C24") (pinfunction "C24_C24") (pintype "passive"))
      (node (ref "X3") (pin "C24") (pinfunction "C24_C24") (pintype "passive"))
      (node (ref "X4") (pin "C24") (pinfunction "C24_C24") (pintype "passive"))
      (node (ref "X5") (pin "C24") (pinfunction "C24_C24") (pintype "passive"))
      (node (ref "X6") (pin "C24") (pinfunction "C24_C24") (pintype "passive"))
      (node (ref "X7") (pin "C24") (pinfunction "C24_C24") (pintype "passive"))
      (node (ref "X8") (pin "C24") (pinfunction "C24_C24") (pintype "passive"))
    )
    (net (code "57") (name "/C25") (class "Default")
      (node (ref "X1") (pin "C25") (pinfunction "C25_C25") (pintype "passive"))
      (node (ref "X2") (pin "C25") (pinfunction "C25_C25") (pintype "passive"))
      (node (ref "X3") (pin "C25") (pinfunction "C25_C25") (pintype "passive"))
      (node (ref "X4") (pin "C25") (pinfunction "C25_C25") (pintype "passive"))
      (node (ref "X5") (pin "C25") (pinfunction "C25_C25") (pintype "passive"))
      (node (ref "X6") (pin "C25") (pinfunction "C25_C25") (pintype "passive"))
      (node (ref "X7") (pin "C25") (pinfunction "C25_C25") (pintype "passive"))
      (node (ref "X8") (pin "C25") (pinfunction "C25_C25") (pintype "passive"))
    )
    (net (code "58") (name "/C26") (class "Default")
      (node (ref "X1") (pin "C26") (pinfunction "C26_C26") (pintype "passive"))
      (node (ref "X2") (pin "C26") (pinfunction "C26_C26") (pintype "passive"))
      (node (ref "X3") (pin "C26") (pinfunction "C26_C26") (pintype "passive"))
      (node (ref "X4") (pin "C26") (pinfunction "C26_C26") (pintype "passive"))
      (node (ref "X5") (pin "C26") (pinfunction "C26_C26") (pintype "passive"))
      (node (ref "X6") (pin "C26") (pinfunction "C26_C26") (pintype "passive"))
      (node (ref "X7") (pin "C26") (pinfunction "C26_C26") (pintype "passive"))
      (node (ref "X8") (pin "C26") (pinfunction "C26_C26") (pintype "passive"))
    )
    (net (code "59") (name "/C27") (class "Default")
      (node (ref "X1") (pin "C27") (pinfunction "C27_C27") (pintype "passive"))
      (node (ref "X2") (pin "C27") (pinfunction "C27_C27") (pintype "passive"))
      (node (ref "X3") (pin "C27") (pinfunction "C27_C27") (pintype "passive"))
      (node (ref "X4") (pin "C27") (pinfunction "C27_C27") (pintype "passive"))
      (node (ref "X5") (pin "C27") (pinfunction "C27_C27") (pintype "passive"))
      (node (ref "X6") (pin "C27") (pinfunction "C27_C27") (pintype "passive"))
      (node (ref "X7") (pin "C27") (pinfunction "C27_C27") (pintype "passive"))
      (node (ref "X8") (pin "C27") (pinfunction "C27_C27") (pintype "passive"))
    )
    (net (code "60") (name "/C28") (class "Default")
      (node (ref "X1") (pin "C28") (pinfunction "C28_C28") (pintype "passive"))
      (node (ref "X2") (pin "C28") (pinfunction "C28_C28") (pintype "passive"))
      (node (ref "X3") (pin "C28") (pinfunction "C28_C28") (pintype "passive"))
      (node (ref "X4") (pin "C28") (pinfunction "C28_C28") (pintype "passive"))
      (node (ref "X5") (pin "C28") (pinfunction "C28_C28") (pintype "passive"))
      (node (ref "X6") (pin "C28") (pinfunction "C28_C28") (pintype "passive"))
      (node (ref "X7") (pin "C28") (pinfunction "C28_C28") (pintype "passive"))
      (node (ref "X8") (pin "C28") (pinfunction "C28_C28") (pintype "passive"))
    )
    (net (code "61") (name "/C29") (class "Default")
      (node (ref "X1") (pin "C29") (pinfunction "C29_C29") (pintype "passive"))
      (node (ref "X2") (pin "C29") (pinfunction "C29_C29") (pintype "passive"))
      (node (ref "X3") (pin "C29") (pinfunction "C29_C29") (pintype "passive"))
      (node (ref "X4") (pin "C29") (pinfunction "C29_C29") (pintype "passive"))
      (node (ref "X5") (pin "C29") (pinfunction "C29_C29") (pintype "passive"))
      (node (ref "X6") (pin "C29") (pinfunction "C29_C29") (pintype "passive"))
      (node (ref "X7") (pin "C29") (pinfunction "C29_C29") (pintype "passive"))
      (node (ref "X8") (pin "C29") (pinfunction "C29_C29") (pintype "passive"))
    )
    (net (code "62") (name "/C30") (class "Default")
      (node (ref "X1") (pin "C30") (pinfunction "C30_C30") (pintype "passive"))
      (node (ref "X2") (pin "C30") (pinfunction "C30_C30") (pintype "passive"))
      (node (ref "X3") (pin "C30") (pinfunction "C30_C30") (pintype "passive"))
      (node (ref "X4") (pin "C30") (pinfunction "C30_C30") (pintype "passive"))
      (node (ref "X5") (pin "C30") (pinfunction "C30_C30") (pintype "passive"))
      (node (ref "X6") (pin "C30") (pinfunction "C30_C30") (pintype "passive"))
      (node (ref "X7") (pin "C30") (pinfunction "C30_C30") (pintype "passive"))
      (node (ref "X8") (pin "C30") (pinfunction "C30_C30") (pintype "passive"))
    )
    (net (code "63") (name "/C31") (class "Default")
      (node (ref "X1") (pin "C31") (pinfunction "C31_C31") (pintype "passive"))
      (node (ref "X2") (pin "C31") (pinfunction "C31_C31") (pintype "passive"))
      (node (ref "X3") (pin "C31") (pinfunction "C31_C31") (pintype "passive"))
      (node (ref "X4") (pin "C31") (pinfunction "C31_C31") (pintype "passive"))
      (node (ref "X5") (pin "C31") (pinfunction "C31_C31") (pintype "passive"))
      (node (ref "X6") (pin "C31") (pinfunction "C31_C31") (pintype "passive"))
      (node (ref "X7") (pin "C31") (pinfunction "C31_C31") (pintype "passive"))
      (node (ref "X8") (pin "C31") (pinfunction "C31_C31") (pintype "passive"))
    )
    (net (code "64") (name "/C32") (class "Default")
      (node (ref "X1") (pin "C32") (pinfunction "C32_C32") (pintype "passive"))
      (node (ref "X2") (pin "C32") (pinfunction "C32_C32") (pintype "passive"))
      (node (ref "X3") (pin "C32") (pinfunction "C32_C32") (pintype "passive"))
      (node (ref "X4") (pin "C32") (pinfunction "C32_C32") (pintype "passive"))
      (node (ref "X5") (pin "C32") (pinfunction "C32_C32") (pintype "passive"))
      (node (ref "X6") (pin "C32") (pinfunction "C32_C32") (pintype "passive"))
      (node (ref "X7") (pin "C32") (pinfunction "C32_C32") (pintype "passive"))
      (node (ref "X8") (pin "C32") (pinfunction "C32_C32") (pintype "passive"))
    )
  )
)
